# BPMLabLineRX23.net
KiCad netlist of a schematic drawn in EAGLE
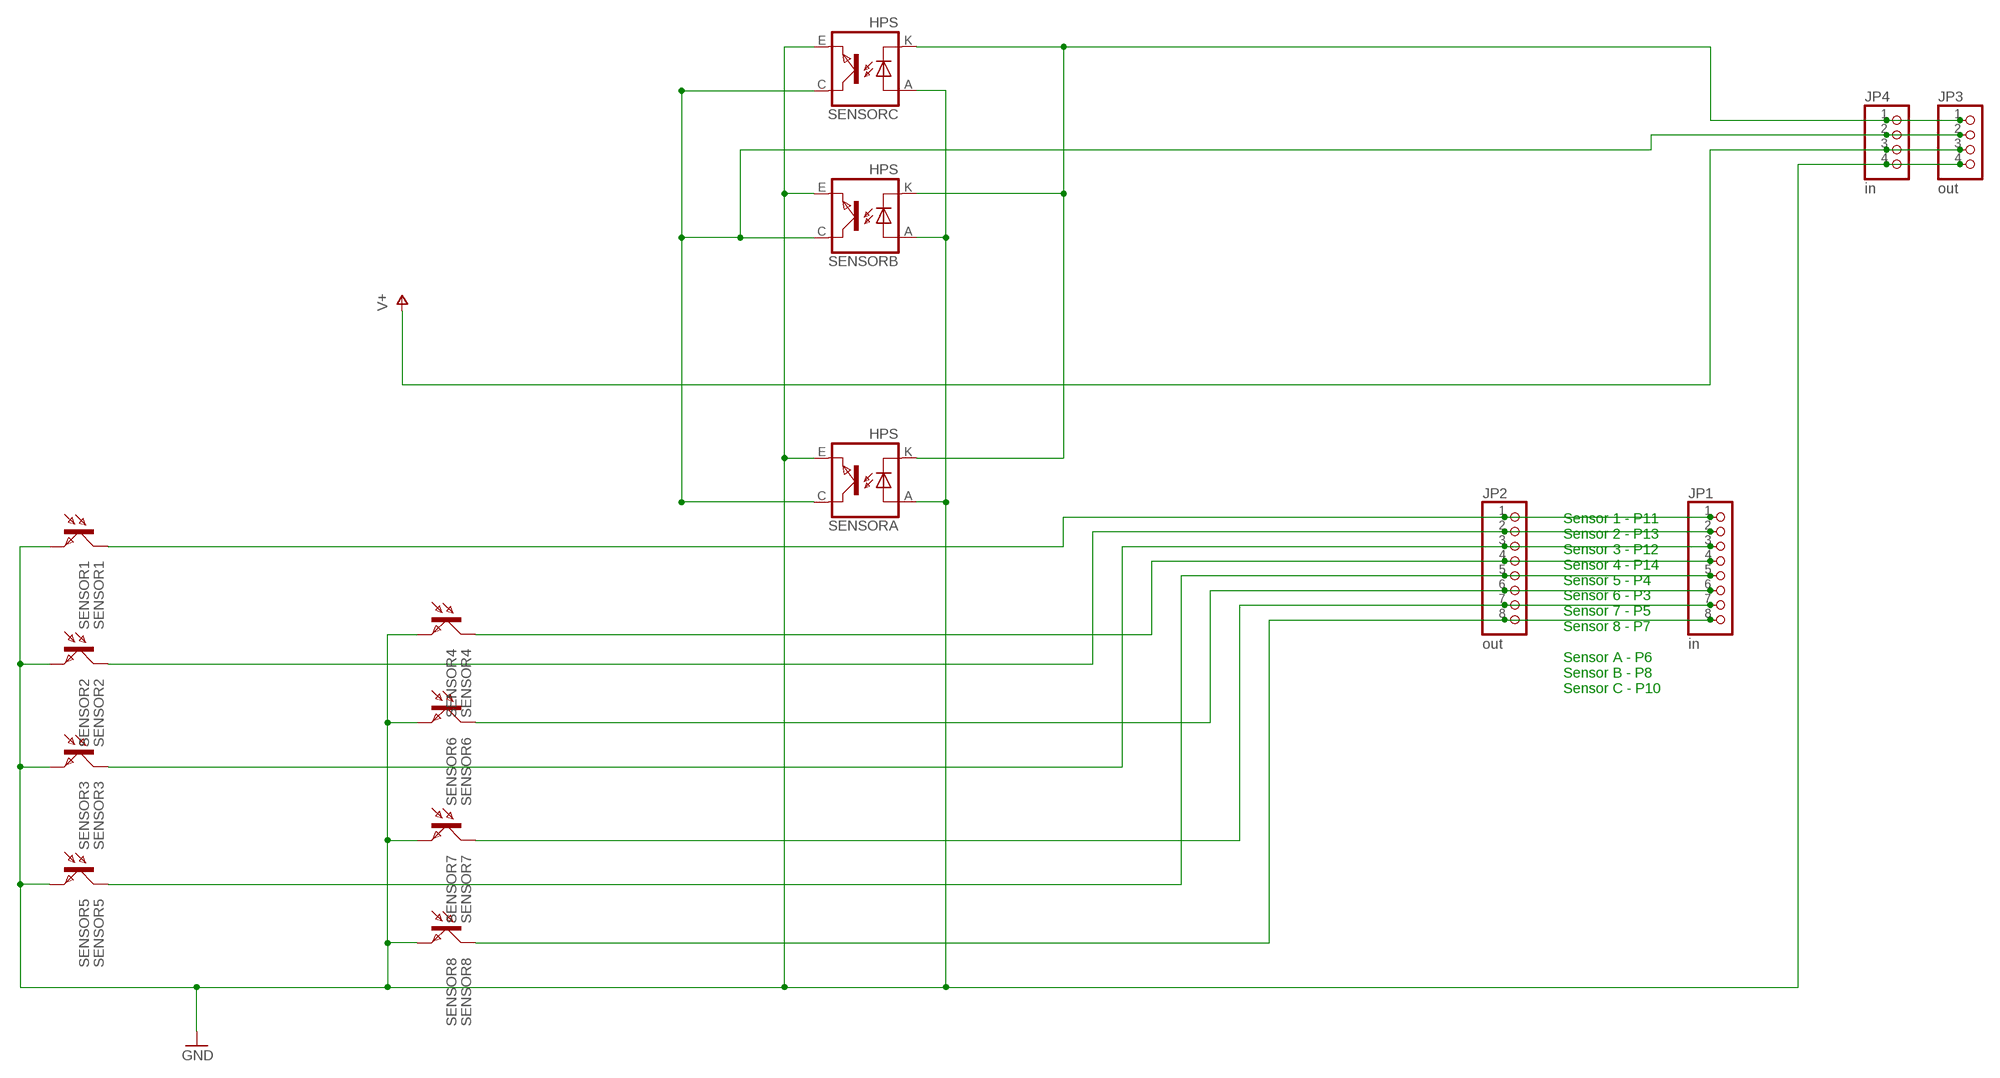
[diagram p0: schematic, sheet 1]

(export (version "E")
  (design (tool "Eeschema 10.0.6"))
  (components
    (comp (ref "JP1")
      (value "in")
      (footprint "eagle-import:1X08")
      (libsource (lib "eagle-import") (part "PINHD-1X8"))
    )
    (comp (ref "JP2")
      (value "out")
      (footprint "eagle-import:1X08")
      (libsource (lib "eagle-import") (part "PINHD-1X8"))
    )
    (comp (ref "JP3")
      (value "out")
      (footprint "eagle-import:1X04")
      (libsource (lib "eagle-import") (part "PINHD-1X4"))
    )
    (comp (ref "JP4")
      (value "in")
      (footprint "eagle-import:1X04")
      (libsource (lib "eagle-import") (part "PINHD-1X4"))
    )
    (comp (ref "SENSOR1")
      (value "SENSOR1")
      (footprint "eagle-import:BPX81")
      (libsource (lib "eagle-import") (part "BPX81"))
    )
    (comp (ref "SENSOR2")
      (value "SENSOR2")
      (footprint "eagle-import:BPX81")
      (libsource (lib "eagle-import") (part "BPX81"))
    )
    (comp (ref "SENSOR3")
      (value "SENSOR3")
      (footprint "eagle-import:BPX81")
      (libsource (lib "eagle-import") (part "BPX81"))
    )
    (comp (ref "SENSOR4")
      (value "SENSOR4")
      (footprint "eagle-import:BPX81")
      (libsource (lib "eagle-import") (part "BPX81"))
    )
    (comp (ref "SENSOR5")
      (value "SENSOR5")
      (footprint "eagle-import:BPX81")
      (libsource (lib "eagle-import") (part "BPX81"))
    )
    (comp (ref "SENSOR6")
      (value "SENSOR6")
      (footprint "eagle-import:BPX81")
      (libsource (lib "eagle-import") (part "BPX81"))
    )
    (comp (ref "SENSOR7")
      (value "SENSOR7")
      (footprint "eagle-import:BPX81")
      (libsource (lib "eagle-import") (part "BPX81"))
    )
    (comp (ref "SENSOR8")
      (value "SENSOR8")
      (footprint "eagle-import:BPX81")
      (libsource (lib "eagle-import") (part "BPX81"))
    )
    (comp (ref "SENSORA")
      (value "HPS")
      (footprint "eagle-import:TCRT5000")
      (libsource (lib "eagle-import") (part "TCRT5000"))
    )
    (comp (ref "SENSORB")
      (value "HPS")
      (footprint "eagle-import:TCRT5000")
      (libsource (lib "eagle-import") (part "TCRT5000"))
    )
    (comp (ref "SENSORC")
      (value "HPS")
      (footprint "eagle-import:TCRT5000")
      (libsource (lib "eagle-import") (part "TCRT5000"))
    )
  )
  (nets
    (net (code "1") (name "GND") (class "Default")
      (node (ref "JP3") (pin "4") (pinfunction "4_4") (pintype "passive"))
      (node (ref "JP4") (pin "4") (pinfunction "4_4") (pintype "passive"))
      (node (ref "SENSOR1") (pin "E") (pinfunction "E_E") (pintype "passive"))
      (node (ref "SENSOR2") (pin "E") (pinfunction "E_E") (pintype "passive"))
      (node (ref "SENSOR3") (pin "E") (pinfunction "E_E") (pintype "passive"))
      (node (ref "SENSOR4") (pin "E") (pinfunction "E_E") (pintype "passive"))
      (node (ref "SENSOR5") (pin "E") (pinfunction "E_E") (pintype "passive"))
      (node (ref "SENSOR6") (pin "E") (pinfunction "E_E") (pintype "passive"))
      (node (ref "SENSOR7") (pin "E") (pinfunction "E_E") (pintype "passive"))
      (node (ref "SENSOR8") (pin "E") (pinfunction "E_E") (pintype "passive"))
      (node (ref "SENSORA") (pin "A") (pinfunction "ANODE_A") (pintype "passive"))
      (node (ref "SENSORA") (pin "E") (pinfunction "EMITTER_E") (pintype "passive"))
      (node (ref "SENSORB") (pin "A") (pinfunction "ANODE_A") (pintype "passive"))
      (node (ref "SENSORB") (pin "E") (pinfunction "EMITTER_E") (pintype "passive"))
      (node (ref "SENSORC") (pin "A") (pinfunction "ANODE_A") (pintype "passive"))
      (node (ref "SENSORC") (pin "E") (pinfunction "EMITTER_E") (pintype "passive"))
    )
    (net (code "2") (name "Net-(JP1-Pad1)") (class "Default")
      (node (ref "JP1") (pin "1") (pinfunction "1_1") (pintype "passive"))
      (node (ref "JP2") (pin "1") (pinfunction "1_1") (pintype "passive"))
      (node (ref "SENSOR1") (pin "C") (pinfunction "C_C") (pintype "passive"))
    )
    (net (code "3") (name "Net-(JP1-Pad2)") (class "Default")
      (node (ref "JP1") (pin "2") (pinfunction "2_2") (pintype "passive"))
      (node (ref "JP2") (pin "2") (pinfunction "2_2") (pintype "passive"))
      (node (ref "SENSOR2") (pin "C") (pinfunction "C_C") (pintype "passive"))
    )
    (net (code "4") (name "Net-(JP1-Pad3)") (class "Default")
      (node (ref "JP1") (pin "3") (pinfunction "3_3") (pintype "passive"))
      (node (ref "JP2") (pin "3") (pinfunction "3_3") (pintype "passive"))
      (node (ref "SENSOR3") (pin "C") (pinfunction "C_C") (pintype "passive"))
    )
    (net (code "5") (name "Net-(JP1-Pad4)") (class "Default")
      (node (ref "JP1") (pin "4") (pinfunction "4_4") (pintype "passive"))
      (node (ref "JP2") (pin "4") (pinfunction "4_4") (pintype "passive"))
      (node (ref "SENSOR4") (pin "C") (pinfunction "C_C") (pintype "passive"))
    )
    (net (code "6") (name "Net-(JP1-Pad5)") (class "Default")
      (node (ref "JP1") (pin "5") (pinfunction "5_5") (pintype "passive"))
      (node (ref "JP2") (pin "5") (pinfunction "5_5") (pintype "passive"))
      (node (ref "SENSOR5") (pin "C") (pinfunction "C_C") (pintype "passive"))
    )
    (net (code "7") (name "Net-(JP1-Pad6)") (class "Default")
      (node (ref "JP1") (pin "6") (pinfunction "6_6") (pintype "passive"))
      (node (ref "JP2") (pin "6") (pinfunction "6_6") (pintype "passive"))
      (node (ref "SENSOR6") (pin "C") (pinfunction "C_C") (pintype "passive"))
    )
    (net (code "8") (name "Net-(JP1-Pad7)") (class "Default")
      (node (ref "JP1") (pin "7") (pinfunction "7_7") (pintype "passive"))
      (node (ref "JP2") (pin "7") (pinfunction "7_7") (pintype "passive"))
      (node (ref "SENSOR7") (pin "C") (pinfunction "C_C") (pintype "passive"))
    )
    (net (code "9") (name "Net-(JP1-Pad8)") (class "Default")
      (node (ref "JP1") (pin "8") (pinfunction "8_8") (pintype "passive"))
      (node (ref "JP2") (pin "8") (pinfunction "8_8") (pintype "passive"))
      (node (ref "SENSOR8") (pin "C") (pinfunction "C_C") (pintype "passive"))
    )
    (net (code "10") (name "Net-(SENSORA-CATHODE)") (class "Default")
      (node (ref "JP3") (pin "1") (pinfunction "1_1") (pintype "passive"))
      (node (ref "JP4") (pin "1") (pinfunction "1_1") (pintype "passive"))
      (node (ref "SENSORA") (pin "K") (pinfunction "CATHODE_K") (pintype "passive"))
      (node (ref "SENSORB") (pin "K") (pinfunction "CATHODE_K") (pintype "passive"))
      (node (ref "SENSORC") (pin "K") (pinfunction "CATHODE_K") (pintype "passive"))
    )
    (net (code "11") (name "Net-(SENSORA-COLLECTOR)") (class "Default")
      (node (ref "JP3") (pin "2") (pinfunction "2_2") (pintype "passive"))
      (node (ref "JP4") (pin "2") (pinfunction "2_2") (pintype "passive"))
      (node (ref "SENSORA") (pin "C") (pinfunction "COLLECTOR_C") (pintype "passive"))
      (node (ref "SENSORB") (pin "C") (pinfunction "COLLECTOR_C") (pintype "passive"))
      (node (ref "SENSORC") (pin "C") (pinfunction "COLLECTOR_C") (pintype "passive"))
    )
    (net (code "12") (name "V+") (class "Default")
      (node (ref "JP3") (pin "3") (pinfunction "3_3") (pintype "passive"))
      (node (ref "JP4") (pin "3") (pinfunction "3_3") (pintype "passive"))
    )
  )
)
